# A100C.net
KiCad netlist of a schematic drawn in EAGLE
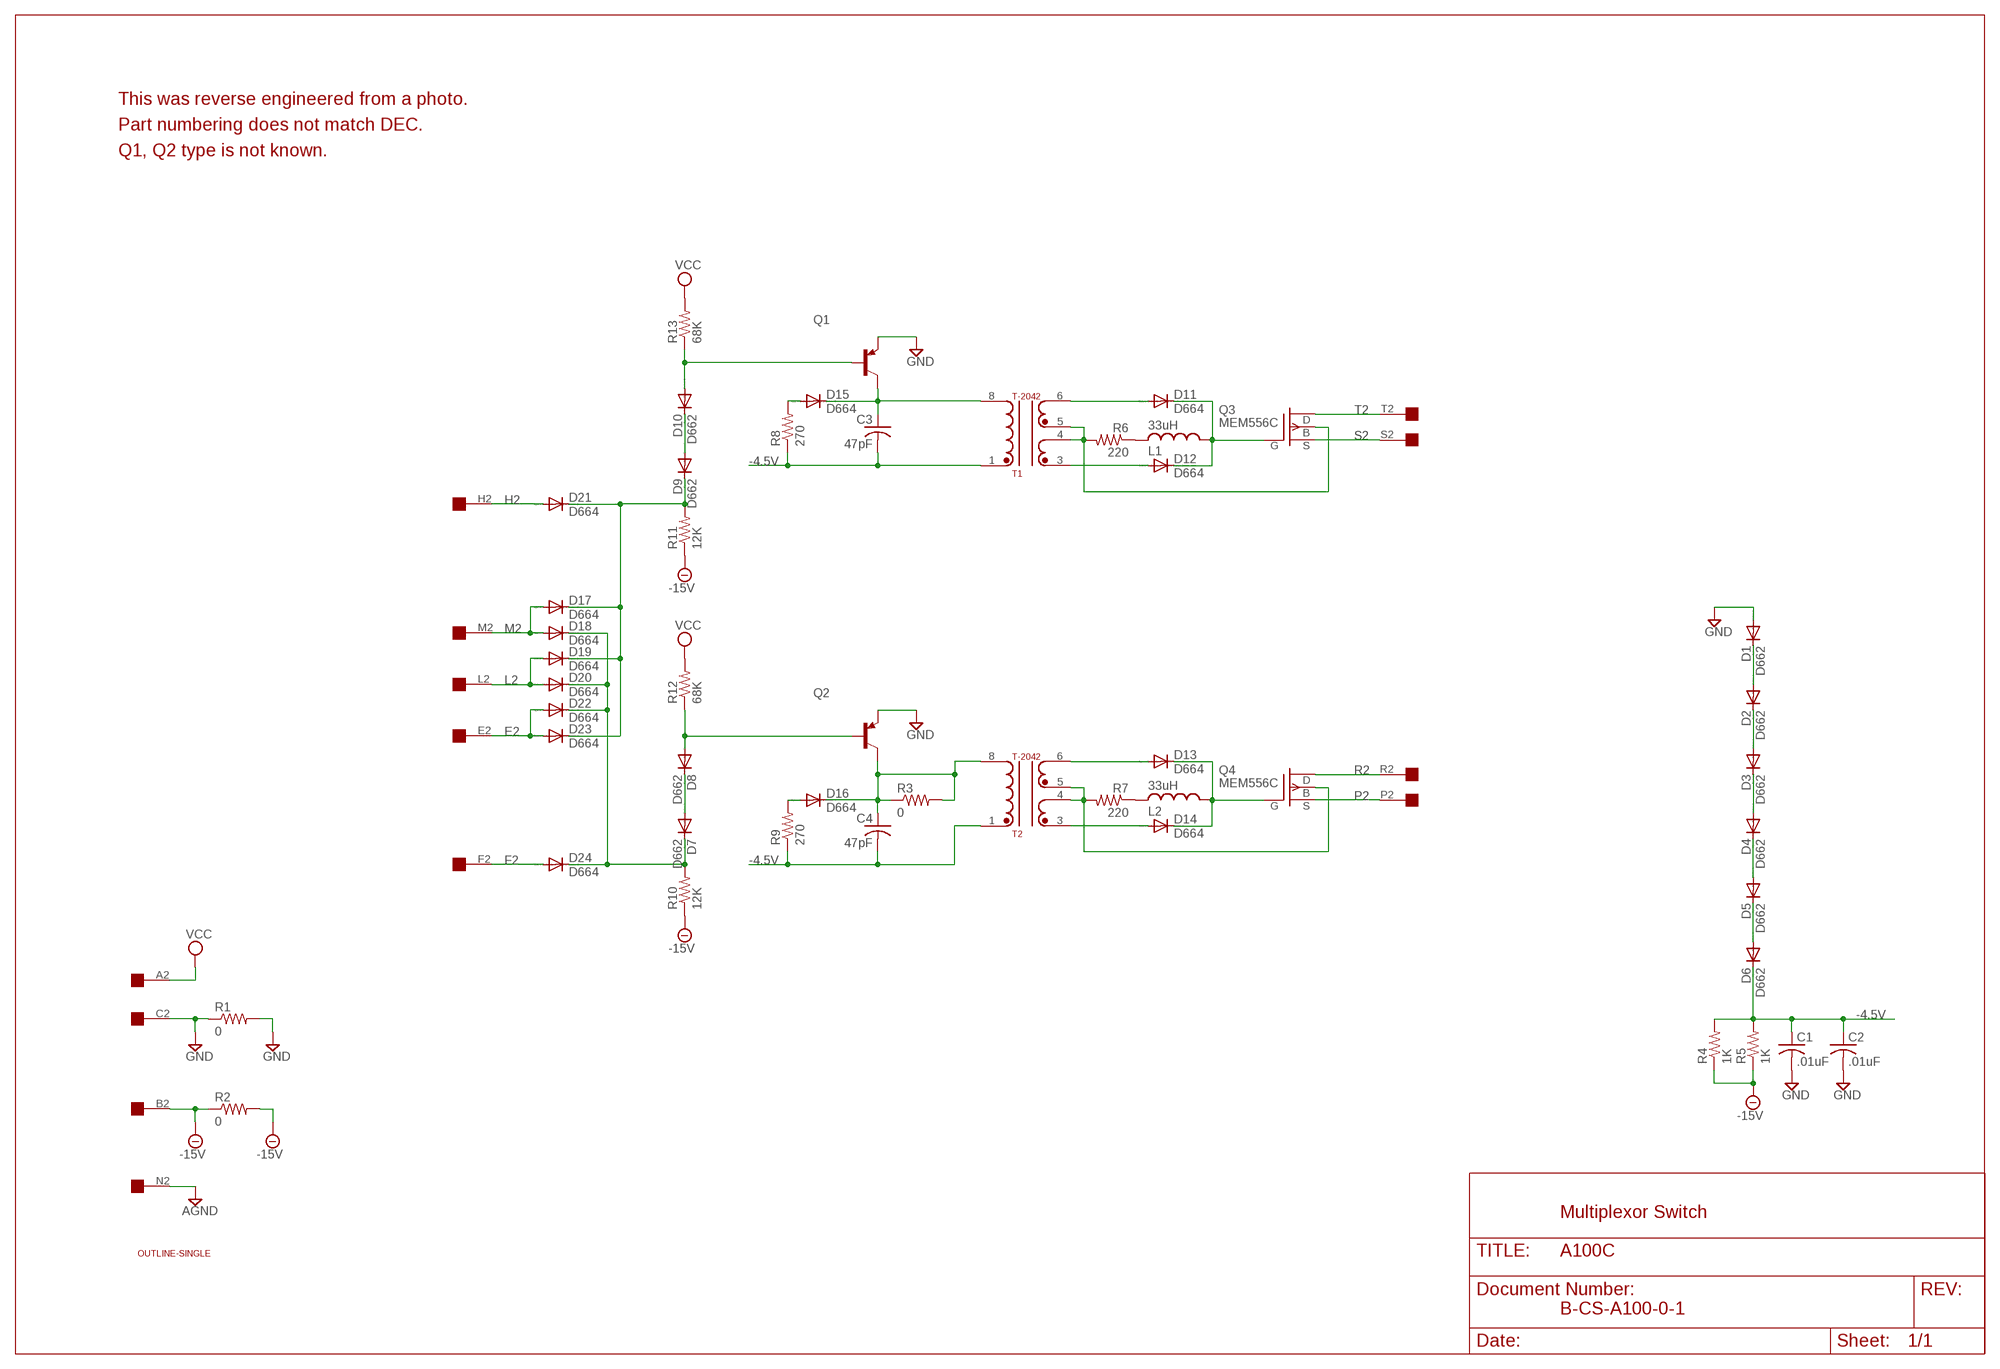
[diagram p0: schematic, sheet 1]

(export (version "E")
  (design (tool "Eeschema 10.0.6"))
  (components
    (comp (ref "C1")
      (value ".01uF")
      (footprint "eagle-import:C063-025X075")
      (libsource (lib "eagle-import") (part "C-US"))
    )
    (comp (ref "C2")
      (value ".01uF")
      (footprint "eagle-import:C063-025X075")
      (libsource (lib "eagle-import") (part "C-US"))
    )
    (comp (ref "C3")
      (value "47pF")
      (footprint "eagle-import:C063-025X075")
      (libsource (lib "eagle-import") (part "C-US"))
    )
    (comp (ref "C4")
      (value "47pF")
      (footprint "eagle-import:C063-025X075")
      (libsource (lib "eagle-import") (part "C-US"))
    )
    (comp (ref "D1")
      (value "D662")
      (footprint "eagle-import:DO35-10")
      (libsource (lib "eagle-import") (part "DIODE-DO35-10"))
    )
    (comp (ref "D2")
      (value "D662")
      (footprint "eagle-import:DO35-10")
      (libsource (lib "eagle-import") (part "DIODE-DO35-10"))
    )
    (comp (ref "D3")
      (value "D662")
      (footprint "eagle-import:DO35-10")
      (libsource (lib "eagle-import") (part "DIODE-DO35-10"))
    )
    (comp (ref "D4")
      (value "D662")
      (footprint "eagle-import:DO35-10")
      (libsource (lib "eagle-import") (part "DIODE-DO35-10"))
    )
    (comp (ref "D5")
      (value "D662")
      (footprint "eagle-import:DO35-10")
      (libsource (lib "eagle-import") (part "DIODE-DO35-10"))
    )
    (comp (ref "D6")
      (value "D662")
      (footprint "eagle-import:DO35-10")
      (libsource (lib "eagle-import") (part "DIODE-DO35-10"))
    )
    (comp (ref "D7")
      (value "D662")
      (footprint "eagle-import:DO35-10")
      (libsource (lib "eagle-import") (part "DIODE-DO35-10"))
    )
    (comp (ref "D8")
      (value "D662")
      (footprint "eagle-import:DO35-10")
      (libsource (lib "eagle-import") (part "DIODE-DO35-10"))
    )
    (comp (ref "D9")
      (value "D662")
      (footprint "eagle-import:DO35-10")
      (libsource (lib "eagle-import") (part "DIODE-DO35-10"))
    )
    (comp (ref "D10")
      (value "D662")
      (footprint "eagle-import:DO35-10")
      (libsource (lib "eagle-import") (part "DIODE-DO35-10"))
    )
    (comp (ref "D11")
      (value "D664")
      (footprint "eagle-import:DO35-10")
      (libsource (lib "eagle-import") (part "DIODE-DO35-10"))
    )
    (comp (ref "D12")
      (value "D664")
      (footprint "eagle-import:DO35-10")
      (libsource (lib "eagle-import") (part "DIODE-DO35-10"))
    )
    (comp (ref "D13")
      (value "D664")
      (footprint "eagle-import:DO35-10")
      (libsource (lib "eagle-import") (part "DIODE-DO35-10"))
    )
    (comp (ref "D14")
      (value "D664")
      (footprint "eagle-import:DO35-10")
      (libsource (lib "eagle-import") (part "DIODE-DO35-10"))
    )
    (comp (ref "D15")
      (value "D664")
      (footprint "eagle-import:DO35-10")
      (libsource (lib "eagle-import") (part "DIODE-DO35-10"))
    )
    (comp (ref "D16")
      (value "D664")
      (footprint "eagle-import:DO35-10")
      (libsource (lib "eagle-import") (part "DIODE-DO35-10"))
    )
    (comp (ref "D17")
      (value "D664")
      (footprint "eagle-import:DO35-10")
      (libsource (lib "eagle-import") (part "DIODE-DO35-10"))
    )
    (comp (ref "D18")
      (value "D664")
      (footprint "eagle-import:DO35-10")
      (libsource (lib "eagle-import") (part "DIODE-DO35-10"))
    )
    (comp (ref "D19")
      (value "D664")
      (footprint "eagle-import:DO35-10")
      (libsource (lib "eagle-import") (part "DIODE-DO35-10"))
    )
    (comp (ref "D20")
      (value "D664")
      (footprint "eagle-import:DO35-10")
      (libsource (lib "eagle-import") (part "DIODE-DO35-10"))
    )
    (comp (ref "D21")
      (value "D664")
      (footprint "eagle-import:DO35-10")
      (libsource (lib "eagle-import") (part "DIODE-DO35-10"))
    )
    (comp (ref "D22")
      (value "D664")
      (footprint "eagle-import:DO35-10")
      (libsource (lib "eagle-import") (part "DIODE-DO35-10"))
    )
    (comp (ref "D23")
      (value "D664")
      (footprint "eagle-import:DO35-10")
      (libsource (lib "eagle-import") (part "DIODE-DO35-10"))
    )
    (comp (ref "D24")
      (value "D664")
      (footprint "eagle-import:DO35-10")
      (libsource (lib "eagle-import") (part "DIODE-DO35-10"))
    )
    (comp (ref "L1")
      (value "33uH")
      (footprint "eagle-import:0207_15")
      (libsource (lib "eagle-import") (part "L-US0207/15"))
    )
    (comp (ref "L2")
      (value "33uH")
      (footprint "eagle-import:0207_15")
      (libsource (lib "eagle-import") (part "L-US0207/15"))
    )
    (comp (ref "Q1")
      (value "-PNP-TO5")
      (footprint "eagle-import:TO5")
      (libsource (lib "eagle-import") (part "-PNP-TO5"))
    )
    (comp (ref "Q2")
      (value "-PNP-TO5")
      (footprint "eagle-import:TO5")
      (libsource (lib "eagle-import") (part "-PNP-TO5"))
    )
    (comp (ref "Q3")
      (value "MEM556C")
      (footprint "eagle-import:TO72")
      (libsource (lib "eagle-import") (part "MEM556C"))
    )
    (comp (ref "Q4")
      (value "MEM556C")
      (footprint "eagle-import:TO72")
      (libsource (lib "eagle-import") (part "MEM556C"))
    )
    (comp (ref "R1")
      (value "0")
      (footprint "eagle-import:0207_10")
      (libsource (lib "eagle-import") (part "R-US_0207/10"))
    )
    (comp (ref "R2")
      (value "0")
      (footprint "eagle-import:0207_10")
      (libsource (lib "eagle-import") (part "R-US_0207/10"))
    )
    (comp (ref "R3")
      (value "0")
      (footprint "eagle-import:0207_10")
      (libsource (lib "eagle-import") (part "R-US_0207/10"))
    )
    (comp (ref "R4")
      (value "1K")
      (footprint "eagle-import:0207_10")
      (libsource (lib "eagle-import") (part "R-US_0207/10"))
    )
    (comp (ref "R5")
      (value "1K")
      (footprint "eagle-import:0207_10")
      (libsource (lib "eagle-import") (part "R-US_0207/10"))
    )
    (comp (ref "R6")
      (value "220")
      (footprint "eagle-import:0207_10")
      (libsource (lib "eagle-import") (part "R-US_0207/10"))
    )
    (comp (ref "R7")
      (value "220")
      (footprint "eagle-import:0207_10")
      (libsource (lib "eagle-import") (part "R-US_0207/10"))
    )
    (comp (ref "R8")
      (value "270")
      (footprint "eagle-import:0207_10")
      (libsource (lib "eagle-import") (part "R-US_0207/10"))
    )
    (comp (ref "R9")
      (value "270")
      (footprint "eagle-import:0207_10")
      (libsource (lib "eagle-import") (part "R-US_0207/10"))
    )
    (comp (ref "R10")
      (value "12K")
      (footprint "eagle-import:0207_10")
      (libsource (lib "eagle-import") (part "R-US_0207/10"))
    )
    (comp (ref "R11")
      (value "12K")
      (footprint "eagle-import:0207_10")
      (libsource (lib "eagle-import") (part "R-US_0207/10"))
    )
    (comp (ref "R12")
      (value "68K")
      (footprint "eagle-import:0207_10")
      (libsource (lib "eagle-import") (part "R-US_0207/10"))
    )
    (comp (ref "R13")
      (value "68K")
      (footprint "eagle-import:0207_10")
      (libsource (lib "eagle-import") (part "R-US_0207/10"))
    )
    (comp (ref "T1")
      (value "T-2042")
      (footprint "eagle-import:TRANSFORMER6C")
      (libsource (lib "eagle-import") (part "T-2042"))
    )
    (comp (ref "T2")
      (value "T-2042")
      (footprint "eagle-import:TRANSFORMER6C")
      (libsource (lib "eagle-import") (part "T-2042"))
    )
    (comp (ref "U$1")
      (value "OUTLINE-SINGLE")
      (footprint "eagle-import:SINGLE")
      (libsource (lib "eagle-import") (part "OUTLINE-SINGLE"))
    )
    (comp (ref "U$2")
      (value "EDGE-1")
      (footprint "eagle-import:EDGE-CON1")
      (libsource (lib "eagle-import") (part "EDGE-1"))
    )
  )
  (nets
    (net (code "1") (name "-15V") (class "Default")
      (node (ref "R10") (pin "1") (pinfunction "1_1") (pintype "passive"))
      (node (ref "R11") (pin "1") (pinfunction "1_1") (pintype "passive"))
      (node (ref "R2") (pin "1") (pinfunction "1_1") (pintype "passive"))
      (node (ref "R2") (pin "2") (pinfunction "2_2") (pintype "passive"))
      (node (ref "R4") (pin "1") (pinfunction "1_1") (pintype "passive"))
      (node (ref "R5") (pin "1") (pinfunction "1_1") (pintype "passive"))
      (node (ref "U$2") (pin "B2") (pinfunction "1_B2") (pintype "bidirectional"))
    )
    (net (code "2") (name "/-4.5V") (class "Default")
      (node (ref "C1") (pin "1") (pinfunction "1_1") (pintype "passive"))
      (node (ref "C2") (pin "1") (pinfunction "1_1") (pintype "passive"))
      (node (ref "C3") (pin "2") (pinfunction "2_2") (pintype "passive"))
      (node (ref "C4") (pin "2") (pinfunction "2_2") (pintype "passive"))
      (node (ref "D6") (pin "C") (pinfunction "C_C") (pintype "passive"))
      (node (ref "R4") (pin "2") (pinfunction "2_2") (pintype "passive"))
      (node (ref "R5") (pin "2") (pinfunction "2_2") (pintype "passive"))
      (node (ref "R8") (pin "1") (pinfunction "1_1") (pintype "passive"))
      (node (ref "R9") (pin "1") (pinfunction "1_1") (pintype "passive"))
      (node (ref "T1") (pin "1") (pinfunction "3_1") (pintype "passive"))
      (node (ref "T2") (pin "1") (pinfunction "3_1") (pintype "passive"))
    )
    (net (code "3") (name "/E2") (class "Default")
      (node (ref "D22") (pin "A") (pinfunction "A_A") (pintype "passive"))
      (node (ref "D23") (pin "A") (pinfunction "A_A") (pintype "passive"))
      (node (ref "U$2") (pin "E2") (pinfunction "1_E2") (pintype "bidirectional"))
    )
    (net (code "4") (name "/F2") (class "Default")
      (node (ref "D24") (pin "A") (pinfunction "A_A") (pintype "passive"))
      (node (ref "U$2") (pin "F2") (pinfunction "1_F2") (pintype "bidirectional"))
    )
    (net (code "5") (name "/H2") (class "Default")
      (node (ref "D21") (pin "A") (pinfunction "A_A") (pintype "passive"))
      (node (ref "U$2") (pin "H2") (pinfunction "1_H2") (pintype "bidirectional"))
    )
    (net (code "6") (name "/L2") (class "Default")
      (node (ref "D19") (pin "A") (pinfunction "A_A") (pintype "passive"))
      (node (ref "D20") (pin "A") (pinfunction "A_A") (pintype "passive"))
      (node (ref "U$2") (pin "L2") (pinfunction "1_L2") (pintype "bidirectional"))
    )
    (net (code "7") (name "/M2") (class "Default")
      (node (ref "D17") (pin "A") (pinfunction "A_A") (pintype "passive"))
      (node (ref "D18") (pin "A") (pinfunction "A_A") (pintype "passive"))
      (node (ref "U$2") (pin "M2") (pinfunction "1_M2") (pintype "bidirectional"))
    )
    (net (code "8") (name "/P2") (class "Default")
      (node (ref "Q4") (pin "3") (pinfunction "S_3") (pintype "passive"))
      (node (ref "U$2") (pin "P2") (pinfunction "1_P2") (pintype "bidirectional"))
    )
    (net (code "9") (name "/R2") (class "Default")
      (node (ref "Q4") (pin "2") (pinfunction "D_2") (pintype "passive"))
      (node (ref "U$2") (pin "R2") (pinfunction "1_R2") (pintype "bidirectional"))
    )
    (net (code "10") (name "/S2") (class "Default")
      (node (ref "Q3") (pin "3") (pinfunction "S_3") (pintype "passive"))
      (node (ref "U$2") (pin "S2") (pinfunction "1_S2") (pintype "bidirectional"))
    )
    (net (code "11") (name "/T2") (class "Default")
      (node (ref "Q3") (pin "2") (pinfunction "D_2") (pintype "passive"))
      (node (ref "U$2") (pin "T2") (pinfunction "1_T2") (pintype "bidirectional"))
    )
    (net (code "12") (name "AGND") (class "Default")
      (node (ref "U$2") (pin "N2") (pinfunction "1_N2") (pintype "bidirectional"))
    )
    (net (code "13") (name "GND") (class "Default")
      (node (ref "C1") (pin "2") (pinfunction "2_2") (pintype "passive"))
      (node (ref "C2") (pin "2") (pinfunction "2_2") (pintype "passive"))
      (node (ref "D1") (pin "A") (pinfunction "A_A") (pintype "passive"))
      (node (ref "Q1") (pin "1") (pinfunction "E_1") (pintype "passive"))
      (node (ref "Q2") (pin "1") (pinfunction "E_1") (pintype "passive"))
      (node (ref "R1") (pin "1") (pinfunction "1_1") (pintype "passive"))
      (node (ref "R1") (pin "2") (pinfunction "2_2") (pintype "passive"))
      (node (ref "U$2") (pin "C2") (pinfunction "1_C2") (pintype "bidirectional"))
    )
    (net (code "14") (name "Net-(D1-PadC)") (class "Default")
      (node (ref "D1") (pin "C") (pinfunction "C_C") (pintype "passive"))
      (node (ref "D2") (pin "A") (pinfunction "A_A") (pintype "passive"))
    )
    (net (code "15") (name "Net-(D2-PadC)") (class "Default")
      (node (ref "D2") (pin "C") (pinfunction "C_C") (pintype "passive"))
      (node (ref "D3") (pin "A") (pinfunction "A_A") (pintype "passive"))
    )
    (net (code "16") (name "Net-(D3-PadC)") (class "Default")
      (node (ref "D3") (pin "C") (pinfunction "C_C") (pintype "passive"))
      (node (ref "D4") (pin "A") (pinfunction "A_A") (pintype "passive"))
    )
    (net (code "17") (name "Net-(D4-PadC)") (class "Default")
      (node (ref "D4") (pin "C") (pinfunction "C_C") (pintype "passive"))
      (node (ref "D5") (pin "A") (pinfunction "A_A") (pintype "passive"))
    )
    (net (code "18") (name "Net-(D5-PadC)") (class "Default")
      (node (ref "D5") (pin "C") (pinfunction "C_C") (pintype "passive"))
      (node (ref "D6") (pin "A") (pinfunction "A_A") (pintype "passive"))
    )
    (net (code "19") (name "Net-(D7-PadA)") (class "Default")
      (node (ref "D7") (pin "A") (pinfunction "A_A") (pintype "passive"))
      (node (ref "D8") (pin "C") (pinfunction "C_C") (pintype "passive"))
    )
    (net (code "20") (name "Net-(D10-PadC)") (class "Default")
      (node (ref "D10") (pin "C") (pinfunction "C_C") (pintype "passive"))
      (node (ref "D9") (pin "A") (pinfunction "A_A") (pintype "passive"))
    )
    (net (code "21") (name "Net-(D11-PadA)") (class "Default")
      (node (ref "D11") (pin "A") (pinfunction "A_A") (pintype "passive"))
      (node (ref "T1") (pin "6") (pinfunction "6_6") (pintype "passive"))
    )
    (net (code "22") (name "Net-(D13-PadA)") (class "Default")
      (node (ref "D13") (pin "A") (pinfunction "A_A") (pintype "passive"))
      (node (ref "T2") (pin "6") (pinfunction "6_6") (pintype "passive"))
    )
    (net (code "23") (name "Net-(D15-PadA)") (class "Default")
      (node (ref "D15") (pin "A") (pinfunction "A_A") (pintype "passive"))
      (node (ref "R8") (pin "2") (pinfunction "2_2") (pintype "passive"))
    )
    (net (code "24") (name "Net-(D16-PadA)") (class "Default")
      (node (ref "D16") (pin "A") (pinfunction "A_A") (pintype "passive"))
      (node (ref "R9") (pin "2") (pinfunction "2_2") (pintype "passive"))
    )
    (net (code "25") (name "Net-(D17-PadC)") (class "Default")
      (node (ref "D17") (pin "C") (pinfunction "C_C") (pintype "passive"))
      (node (ref "D19") (pin "C") (pinfunction "C_C") (pintype "passive"))
      (node (ref "D21") (pin "C") (pinfunction "C_C") (pintype "passive"))
      (node (ref "D23") (pin "C") (pinfunction "C_C") (pintype "passive"))
      (node (ref "D9") (pin "C") (pinfunction "C_C") (pintype "passive"))
      (node (ref "R11") (pin "2") (pinfunction "2_2") (pintype "passive"))
    )
    (net (code "26") (name "Net-(D18-PadC)") (class "Default")
      (node (ref "D18") (pin "C") (pinfunction "C_C") (pintype "passive"))
      (node (ref "D20") (pin "C") (pinfunction "C_C") (pintype "passive"))
      (node (ref "D22") (pin "C") (pinfunction "C_C") (pintype "passive"))
      (node (ref "D24") (pin "C") (pinfunction "C_C") (pintype "passive"))
      (node (ref "D7") (pin "C") (pinfunction "C_C") (pintype "passive"))
      (node (ref "R10") (pin "2") (pinfunction "2_2") (pintype "passive"))
    )
    (net (code "27") (name "Net-(L1-Pad2)") (class "Default")
      (node (ref "L1") (pin "2") (pinfunction "2_2") (pintype "passive"))
      (node (ref "R6") (pin "1") (pinfunction "1_1") (pintype "passive"))
    )
    (net (code "28") (name "Net-(L2-Pad2)") (class "Default")
      (node (ref "L2") (pin "2") (pinfunction "2_2") (pintype "passive"))
      (node (ref "R7") (pin "1") (pinfunction "1_1") (pintype "passive"))
    )
    (net (code "29") (name "Net-(Q1-B)") (class "Default")
      (node (ref "D10") (pin "A") (pinfunction "A_A") (pintype "passive"))
      (node (ref "Q1") (pin "2") (pinfunction "B_2") (pintype "passive"))
      (node (ref "R13") (pin "1") (pinfunction "1_1") (pintype "passive"))
    )
    (net (code "30") (name "Net-(Q1-C)") (class "Default")
      (node (ref "C3") (pin "1") (pinfunction "1_1") (pintype "passive"))
      (node (ref "D15") (pin "C") (pinfunction "C_C") (pintype "passive"))
      (node (ref "Q1") (pin "3") (pinfunction "C_3") (pintype "passive"))
      (node (ref "T1") (pin "8") (pinfunction "4_8") (pintype "passive"))
    )
    (net (code "31") (name "Net-(Q2-B)") (class "Default")
      (node (ref "D8") (pin "A") (pinfunction "A_A") (pintype "passive"))
      (node (ref "Q2") (pin "2") (pinfunction "B_2") (pintype "passive"))
      (node (ref "R12") (pin "1") (pinfunction "1_1") (pintype "passive"))
    )
    (net (code "32") (name "Net-(Q2-C)") (class "Default")
      (node (ref "C4") (pin "1") (pinfunction "1_1") (pintype "passive"))
      (node (ref "D16") (pin "C") (pinfunction "C_C") (pintype "passive"))
      (node (ref "Q2") (pin "3") (pinfunction "C_3") (pintype "passive"))
      (node (ref "R3") (pin "1") (pinfunction "1_1") (pintype "passive"))
      (node (ref "R3") (pin "2") (pinfunction "2_2") (pintype "passive"))
      (node (ref "T2") (pin "8") (pinfunction "4_8") (pintype "passive"))
    )
    (net (code "33") (name "Net-(Q3-B)") (class "Default")
      (node (ref "Q3") (pin "4") (pinfunction "B_4") (pintype "passive"))
      (node (ref "R6") (pin "2") (pinfunction "2_2") (pintype "passive"))
      (node (ref "T1") (pin "4") (pinfunction "5_4") (pintype "passive"))
      (node (ref "T1") (pin "5") (pinfunction "1_5") (pintype "passive"))
    )
    (net (code "34") (name "Net-(Q3-G)") (class "Default")
      (node (ref "D11") (pin "C") (pinfunction "C_C") (pintype "passive"))
      (node (ref "D12") (pin "C") (pinfunction "C_C") (pintype "passive"))
      (node (ref "L1") (pin "1") (pinfunction "1_1") (pintype "passive"))
      (node (ref "Q3") (pin "1") (pinfunction "G_1") (pintype "passive"))
    )
    (net (code "35") (name "Net-(Q4-B)") (class "Default")
      (node (ref "Q4") (pin "4") (pinfunction "B_4") (pintype "passive"))
      (node (ref "R7") (pin "2") (pinfunction "2_2") (pintype "passive"))
      (node (ref "T2") (pin "4") (pinfunction "5_4") (pintype "passive"))
      (node (ref "T2") (pin "5") (pinfunction "1_5") (pintype "passive"))
    )
    (net (code "36") (name "Net-(Q4-G)") (class "Default")
      (node (ref "D13") (pin "C") (pinfunction "C_C") (pintype "passive"))
      (node (ref "D14") (pin "C") (pinfunction "C_C") (pintype "passive"))
      (node (ref "L2") (pin "1") (pinfunction "1_1") (pintype "passive"))
      (node (ref "Q4") (pin "1") (pinfunction "G_1") (pintype "passive"))
    )
    (net (code "37") (name "Net-(T1-2)") (class "Default")
      (node (ref "D12") (pin "A") (pinfunction "A_A") (pintype "passive"))
      (node (ref "T1") (pin "3") (pinfunction "2_3") (pintype "passive"))
    )
    (net (code "38") (name "Net-(T2-2)") (class "Default")
      (node (ref "D14") (pin "A") (pinfunction "A_A") (pintype "passive"))
      (node (ref "T2") (pin "3") (pinfunction "2_3") (pintype "passive"))
    )
    (net (code "39") (name "VCC") (class "Default")
      (node (ref "R12") (pin "2") (pinfunction "2_2") (pintype "passive"))
      (node (ref "R13") (pin "2") (pinfunction "2_2") (pintype "passive"))
      (node (ref "U$2") (pin "A2") (pinfunction "1_A2") (pintype "bidirectional"))
    )
  )
)
